# Power_SCH.net
KiCad netlist of a schematic drawn in Altium Designer
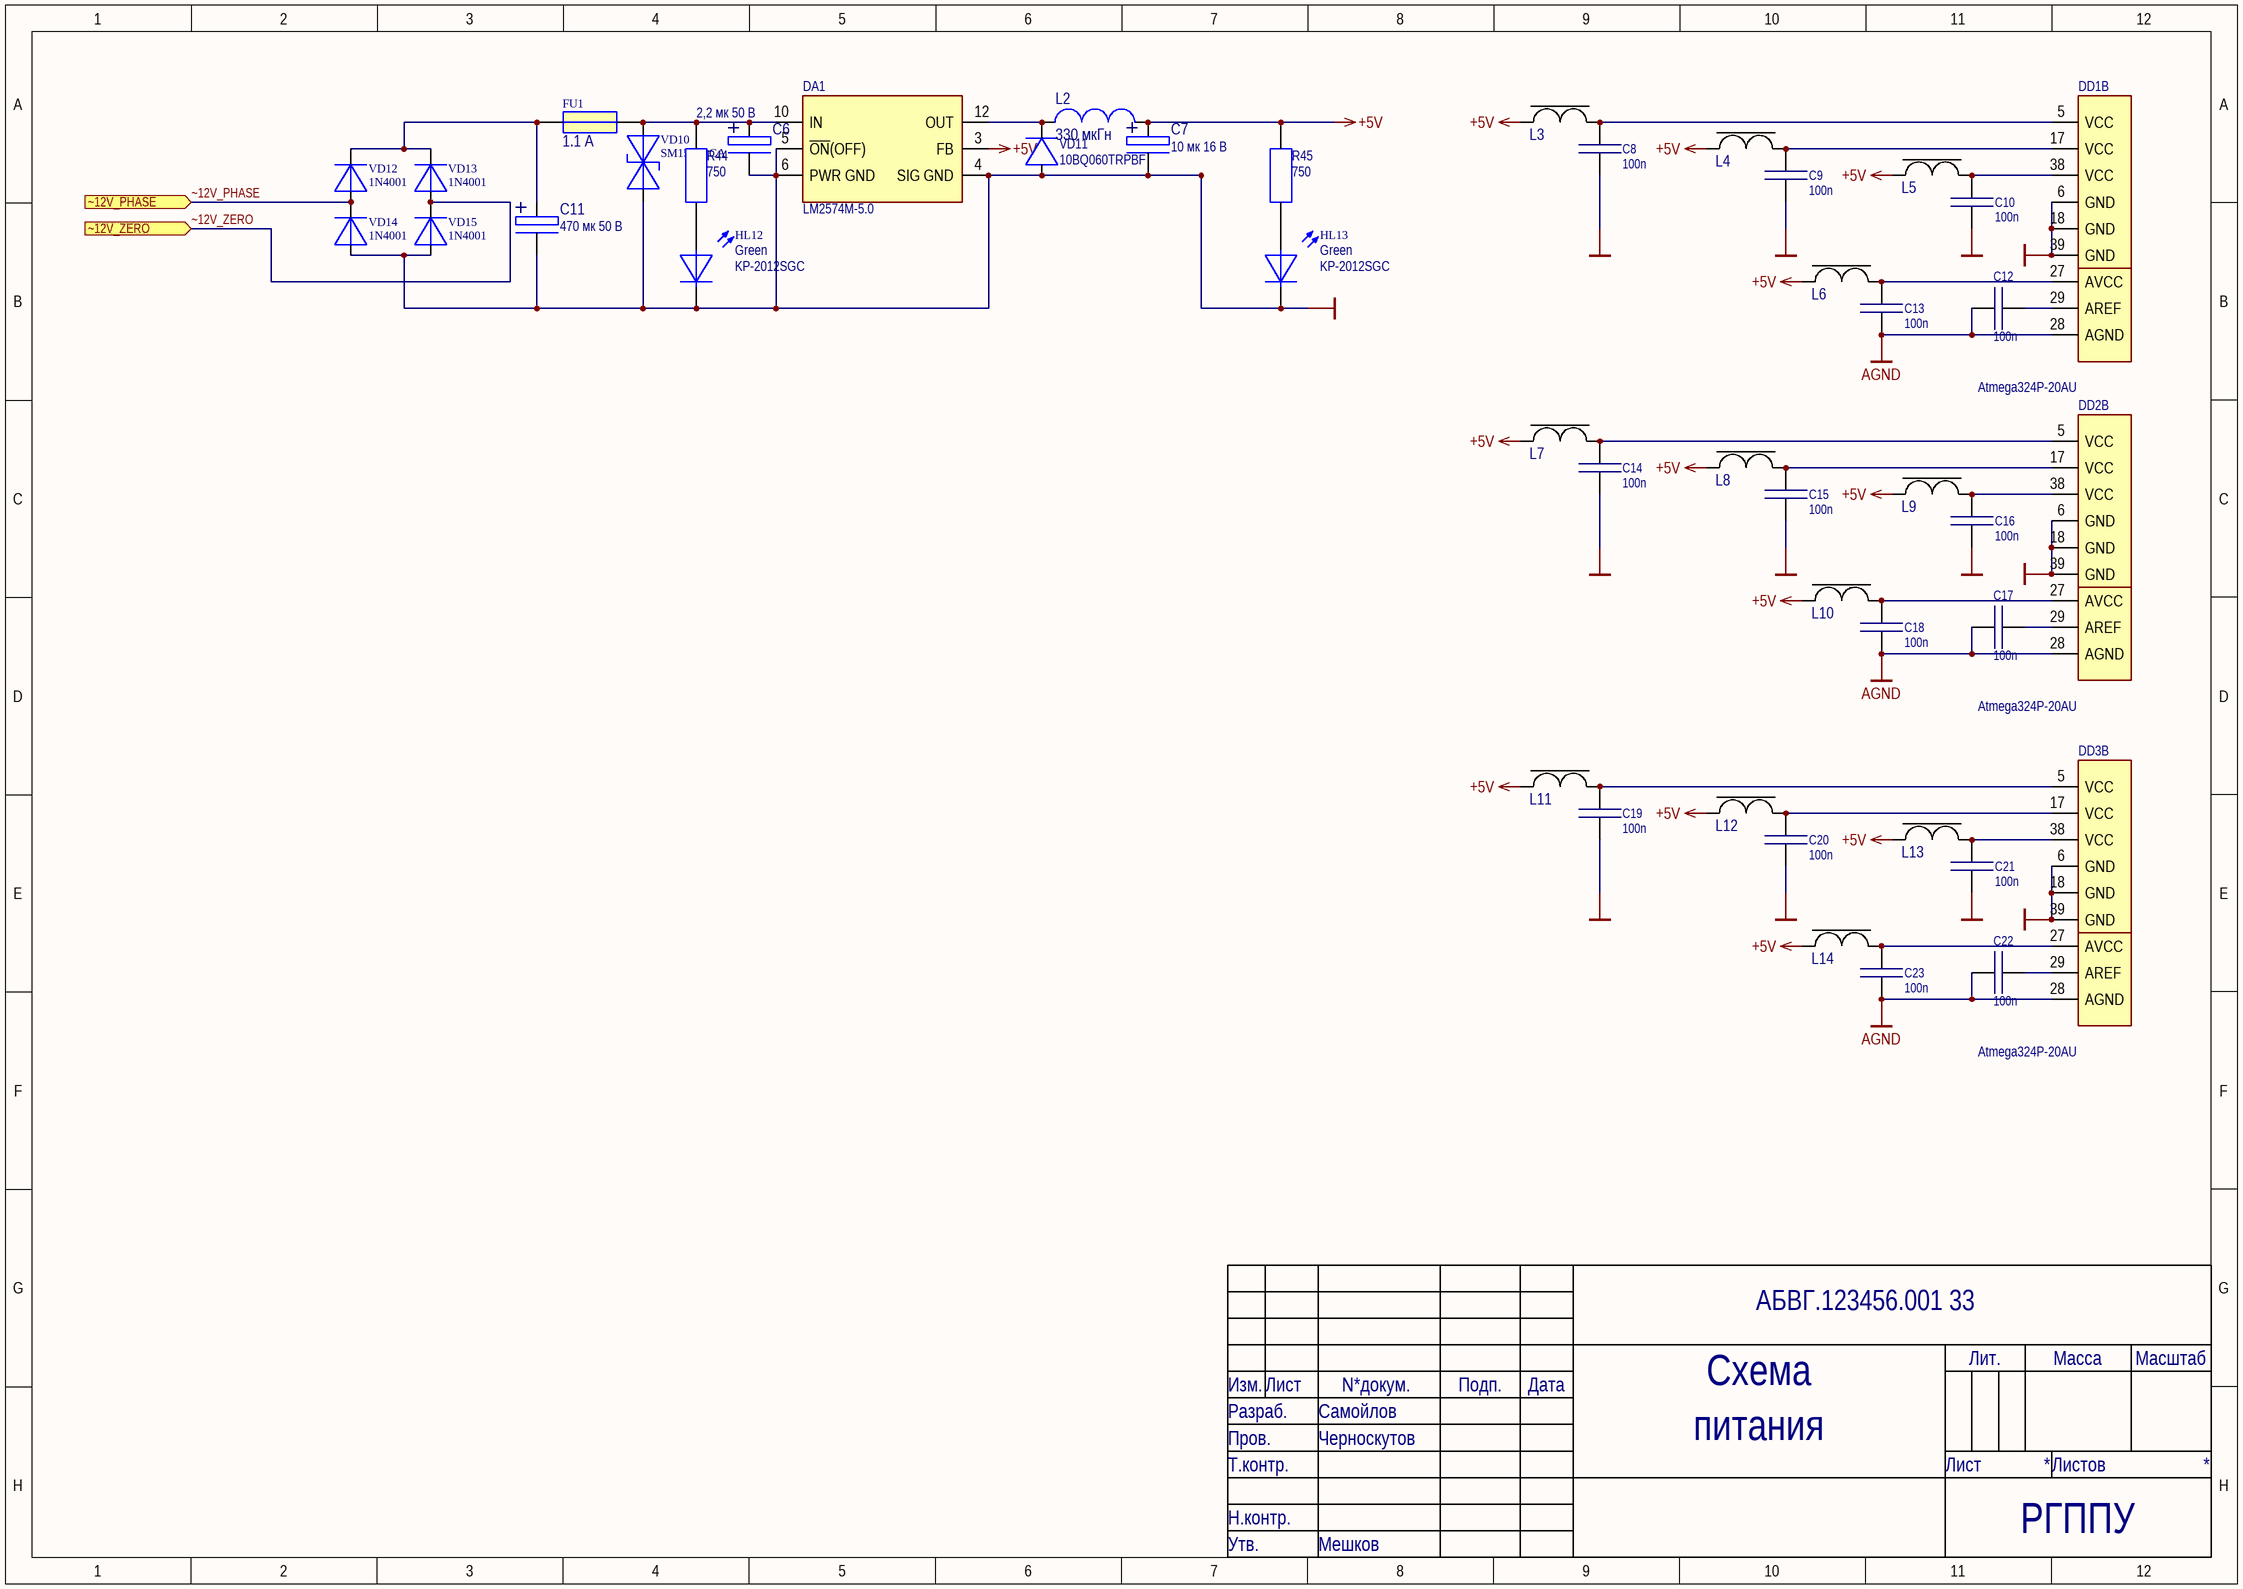
[diagram p0: Power_SCH.SchDoc]

(export (version "E")
  (design (tool "Eeschema 10.0.6"))
  (components
    (comp (ref "C6")
      (value "2,2 мк 50 В")
      (footprint "Cap:CAP_POLAR_ELLYTE_B")
      (description "2,2uF 50V Polar capacitor")
      (fields
        (field (name "MANUFACTURERPARTNUMBER") "CA050M2R20REB-0405")
        (field (name "MANUFACTURER") "Yageo")
      )
      (libsource (lib "Cap") (part "02200_050"))
    )
    (comp (ref "C7")
      (value "10 мк 16 В")
      (footprint "Cap:CAP_POLAR_ELLYTE_B")
      (description "10uF 16V Polar SMD cap")
      (fields
        (field (name "MANUFACTURERPARTNUMBER") "CA016M0010REB-0405")
        (field (name "MANUFACTURER") "YAGEO")
      )
      (libsource (lib "Cap") (part "10000_016"))
    )
    (comp (ref "C8")
      (value "100n")
      (footprint "SMDRC0805")
      (description "Generic capasitor non-polar")
      (fields (field (name "PARTNUMBER") "Capacitor 0805 100n"))
      (libsource (lib "library") (part "Capacitor"))
    )
    (comp (ref "C9")
      (value "100n")
      (footprint "SMDRC0805")
      (description "Generic capasitor non-polar")
      (fields (field (name "PARTNUMBER") "Capacitor 0805 100n"))
      (libsource (lib "library") (part "Capacitor"))
    )
    (comp (ref "C10")
      (value "100n")
      (footprint "SMDRC0805")
      (description "Generic capasitor non-polar")
      (fields (field (name "PARTNUMBER") "Capacitor 0805 100n"))
      (libsource (lib "library") (part "Capacitor"))
    )
    (comp (ref "C11")
      (value "470 мк 50 В")
      (footprint "Cap:CAP_POLAR_10mm")
      (description "470uF 50V Polar capacitor")
      (fields (field (name "MANUFACTURERPARTNUMBER") "CA035M0220REG") (field (name "MANUFACTURER") "Yageo"))
      (libsource (lib "Cap") (part "470000_050"))
    )
    (comp (ref "C12")
      (value "100n")
      (footprint "SMDRC0805")
      (description "Generic capasitor non-polar")
      (fields (field (name "PARTNUMBER") "Capacitor 0805 100n"))
      (libsource (lib "library") (part "Capacitor"))
    )
    (comp (ref "C13")
      (value "100n")
      (footprint "SMDRC0805")
      (description "Generic capasitor non-polar")
      (fields (field (name "PARTNUMBER") "Capacitor 0805 100n"))
      (libsource (lib "library") (part "Capacitor"))
    )
    (comp (ref "C14")
      (value "100n")
      (footprint "SMDRC0805")
      (description "Generic capasitor non-polar")
      (fields (field (name "PARTNUMBER") "Capacitor 0805 100n"))
      (libsource (lib "library") (part "Capacitor"))
    )
    (comp (ref "C15")
      (value "100n")
      (footprint "SMDRC0805")
      (description "Generic capasitor non-polar")
      (fields (field (name "PARTNUMBER") "Capacitor 0805 100n"))
      (libsource (lib "library") (part "Capacitor"))
    )
    (comp (ref "C16")
      (value "100n")
      (footprint "SMDRC0805")
      (description "Generic capasitor non-polar")
      (fields (field (name "PARTNUMBER") "Capacitor 0805 100n"))
      (libsource (lib "library") (part "Capacitor"))
    )
    (comp (ref "C17")
      (value "100n")
      (footprint "SMDRC0805")
      (description "Generic capasitor non-polar")
      (fields (field (name "PARTNUMBER") "Capacitor 0805 100n"))
      (libsource (lib "library") (part "Capacitor"))
    )
    (comp (ref "C18")
      (value "100n")
      (footprint "SMDRC0805")
      (description "Generic capasitor non-polar")
      (fields (field (name "PARTNUMBER") "Capacitor 0805 100n"))
      (libsource (lib "library") (part "Capacitor"))
    )
    (comp (ref "C19")
      (value "100n")
      (footprint "SMDRC0805")
      (description "Generic capasitor non-polar")
      (fields (field (name "PARTNUMBER") "Capacitor 0805 100n"))
      (libsource (lib "library") (part "Capacitor"))
    )
    (comp (ref "C20")
      (value "100n")
      (footprint "SMDRC0805")
      (description "Generic capasitor non-polar")
      (fields (field (name "PARTNUMBER") "Capacitor 0805 100n"))
      (libsource (lib "library") (part "Capacitor"))
    )
    (comp (ref "C21")
      (value "100n")
      (footprint "SMDRC0805")
      (description "Generic capasitor non-polar")
      (fields (field (name "PARTNUMBER") "Capacitor 0805 100n"))
      (libsource (lib "library") (part "Capacitor"))
    )
    (comp (ref "C22")
      (value "100n")
      (footprint "SMDRC0805")
      (description "Generic capasitor non-polar")
      (fields (field (name "PARTNUMBER") "Capacitor 0805 100n"))
      (libsource (lib "library") (part "Capacitor"))
    )
    (comp (ref "C23")
      (value "100n")
      (footprint "SMDRC0805")
      (description "Generic capasitor non-polar")
      (fields (field (name "PARTNUMBER") "Capacitor 0805 100n"))
      (libsource (lib "library") (part "Capacitor"))
    )
    (comp (ref "DA1")
      (value "LM2574M-5.0")
      (footprint "Power:SOIC127P1030X264-14M")
      (fields (field (name "MANUFACTURERPARTNUMBER") "LM2574M-5.0"))
      (libsource (lib "Power") (part "LM2574M-5.0"))
    )
    (comp (ref "DD1")
      (value "Atmega324P-20AU")
      (footprint "Atmel Microcontroller 8-Bit Automotive AVR:44ML_M")
      (description "Microcontroller 8-bit")
      (fields (field (name "MANUFACTURER") "Atmel") (field (name "MANUFACTURERPARTNUMBER") "Atmega324P-20AU"))
      (libsource (lib "Microcontrollers") (part "Atmega324P-20AU"))
    )
    (comp (ref "DD2")
      (value "Atmega324P-20AU")
      (footprint "Atmel Microcontroller 8-Bit Automotive AVR:44ML_M")
      (description "Microcontroller 8-bit")
      (fields (field (name "MANUFACTURER") "Atmel") (field (name "MANUFACTURERPARTNUMBER") "Atmega324P-20AU"))
      (libsource (lib "Microcontrollers") (part "Atmega324P-20AU"))
    )
    (comp (ref "DD3")
      (value "Atmega324P-20AU")
      (footprint "Atmel Microcontroller 8-Bit Automotive AVR:44ML_M")
      (description "Microcontroller 8-bit")
      (fields (field (name "MANUFACTURER") "Atmel") (field (name "MANUFACTURERPARTNUMBER") "Atmega324P-20AU"))
      (libsource (lib "Microcontrollers") (part "Atmega324P-20AU"))
    )
    (comp (ref "FU1")
      (value "1.1 А")
      (footprint "Power:EFuse 1.1A")
      (description "Fuse")
      (fields (field (name "MANUFACTURERPARTNUMBER") "EFuse LP60-110F"))
      (libsource (lib "Power") (part "EFuse LP60-110F"))
    )
    (comp (ref "HL12")
      (value "Green")
      (footprint "Indicator:DIOMELF2012M")
      (description "Diod LED SMD Green")
      (fields (field (name "MANUFACTURERPARTNUMBER") "KP-2012SGC"))
      (libsource (lib "Indicator") (part "LED1_G"))
    )
    (comp (ref "HL13")
      (value "Green")
      (footprint "Indicator:DIOMELF2012M")
      (description "Diod LED SMD Green")
      (fields (field (name "MANUFACTURERPARTNUMBER") "KP-2012SGC"))
      (libsource (lib "Indicator") (part "LED1_G"))
    )
    (comp (ref "L2")
      (value "330 мкГн")
      (footprint "Inductor:INDP7972X50M")
      (description "Inductor")
      (fields (field (name "MANUFACTURERPARTNUMBER") "SCD0705T-331K-N"))
      (libsource (lib "Inductor") (part "SCD0705T-331K-N"))
    )
    (comp (ref "L3")
      (value "MPZ1608S181A")
      (footprint "Inductor:INDC0603X03M")
      (description "Ferrite Bead")
      (libsource (lib "Inductor") (part "Ferrite Bead"))
    )
    (comp (ref "L4")
      (value "MPZ1608S181A")
      (footprint "Inductor:INDC0603X03M")
      (description "Ferrite Bead")
      (libsource (lib "Inductor") (part "Ferrite Bead"))
    )
    (comp (ref "L5")
      (value "MPZ1608S181A")
      (footprint "Inductor:INDC0603X03M")
      (description "Ferrite Bead")
      (libsource (lib "Inductor") (part "Ferrite Bead"))
    )
    (comp (ref "L6")
      (value "MPZ1608S181A")
      (footprint "Inductor:INDC0603X03M")
      (description "Ferrite Bead")
      (libsource (lib "Inductor") (part "Ferrite Bead"))
    )
    (comp (ref "L7")
      (value "MPZ1608S181A")
      (footprint "Inductor:INDC0603X03M")
      (description "Ferrite Bead")
      (libsource (lib "Inductor") (part "Ferrite Bead"))
    )
    (comp (ref "L8")
      (value "MPZ1608S181A")
      (footprint "Inductor:INDC0603X03M")
      (description "Ferrite Bead")
      (libsource (lib "Inductor") (part "Ferrite Bead"))
    )
    (comp (ref "L9")
      (value "MPZ1608S181A")
      (footprint "Inductor:INDC0603X03M")
      (description "Ferrite Bead")
      (libsource (lib "Inductor") (part "Ferrite Bead"))
    )
    (comp (ref "L10")
      (value "MPZ1608S181A")
      (footprint "Inductor:INDC0603X03M")
      (description "Ferrite Bead")
      (libsource (lib "Inductor") (part "Ferrite Bead"))
    )
    (comp (ref "L11")
      (value "MPZ1608S181A")
      (footprint "Inductor:INDC0603X03M")
      (description "Ferrite Bead")
      (libsource (lib "Inductor") (part "Ferrite Bead"))
    )
    (comp (ref "L12")
      (value "MPZ1608S181A")
      (footprint "Inductor:INDC0603X03M")
      (description "Ferrite Bead")
      (libsource (lib "Inductor") (part "Ferrite Bead"))
    )
    (comp (ref "L13")
      (value "MPZ1608S181A")
      (footprint "Inductor:INDC0603X03M")
      (description "Ferrite Bead")
      (libsource (lib "Inductor") (part "Ferrite Bead"))
    )
    (comp (ref "L14")
      (value "MPZ1608S181A")
      (footprint "Inductor:INDC0603X03M")
      (description "Ferrite Bead")
      (libsource (lib "Inductor") (part "Ferrite Bead"))
    )
    (comp (ref "R44")
      (value "750")
      (footprint "SMDRC0805")
      (description "Generic resistor")
      (fields (field (name "PARTNUMBER") "Resistor 0805 750"))
      (libsource (lib "library") (part "Resistor"))
    )
    (comp (ref "R45")
      (value "750")
      (footprint "SMDRC0805")
      (description "Generic resistor")
      (fields (field (name "PARTNUMBER") "Resistor 0805 750"))
      (libsource (lib "library") (part "Resistor"))
    )
    (comp (ref "VD10")
      (value "SM15T12CA")
      (footprint "DIod:SUPRES3216X18N")
      (description "Diod suppressor")
      (fields
        (field (name "MANUFACTURER") "ST Microelectronics")
        (field (name "MANUFACTURERPARTNUMBER") "SM15T12CA")
      )
      (libsource (lib "Diod") (part "SM15T12CA"))
    )
    (comp (ref "VD11")
      (value "10BQ060TRPBF")
      (footprint "DIod:SHOTKY 4.1x3.3")
      (description "DIODE SCHOTTKY 60V 1A DO214AA")
      (fields
        (field (name "MANUFACTURER") "Vishay Semiconductor Diodes Division")
        (field (name "MANUFACTURERPARTNUMBER") "10BQ060TRPBF")
      )
      (libsource (lib "Diod") (part "10BQ060TRPBF"))
    )
    (comp (ref "VD12")
      (value "1N4001")
      (footprint "DIod:PinDiode")
      (description "Rectifying diode")
      (fields (field (name "MANUFACTURERPARTNUMBER") "1N4001"))
      (libsource (lib "Diod") (part "1N4001"))
    )
    (comp (ref "VD13")
      (value "1N4001")
      (footprint "DIod:PinDiode")
      (description "Rectifying diode")
      (fields (field (name "MANUFACTURERPARTNUMBER") "1N4001"))
      (libsource (lib "Diod") (part "1N4001"))
    )
    (comp (ref "VD14")
      (value "1N4001")
      (footprint "DIod:PinDiode")
      (description "Rectifying diode")
      (fields (field (name "MANUFACTURERPARTNUMBER") "1N4001"))
      (libsource (lib "Diod") (part "1N4001"))
    )
    (comp (ref "VD15")
      (value "1N4001")
      (footprint "DIod:PinDiode")
      (description "Rectifying diode")
      (fields (field (name "MANUFACTURERPARTNUMBER") "1N4001"))
      (libsource (lib "Diod") (part "1N4001"))
    )
  )
  (nets
    (net (code "1") (name "+5V") (class "Default")
      (node (ref "C7") (pin "2") (pinfunction "+_2") (pintype "passive"))
      (node (ref "DA1") (pin "3") (pinfunction "FB_3") (pintype "passive"))
      (node (ref "L10") (pin "1") (pinfunction "1_1") (pintype "passive"))
      (node (ref "L11") (pin "1") (pinfunction "1_1") (pintype "passive"))
      (node (ref "L12") (pin "1") (pinfunction "1_1") (pintype "passive"))
      (node (ref "L13") (pin "1") (pinfunction "1_1") (pintype "passive"))
      (node (ref "L14") (pin "1") (pinfunction "1_1") (pintype "passive"))
      (node (ref "L2") (pin "1") (pinfunction "1_1") (pintype "passive"))
      (node (ref "L3") (pin "1") (pinfunction "1_1") (pintype "passive"))
      (node (ref "L4") (pin "1") (pinfunction "1_1") (pintype "passive"))
      (node (ref "L5") (pin "1") (pinfunction "1_1") (pintype "passive"))
      (node (ref "L6") (pin "1") (pinfunction "1_1") (pintype "passive"))
      (node (ref "L7") (pin "1") (pinfunction "1_1") (pintype "passive"))
      (node (ref "L8") (pin "1") (pinfunction "1_1") (pintype "passive"))
      (node (ref "L9") (pin "1") (pinfunction "1_1") (pintype "passive"))
      (node (ref "R45") (pin "2") (pinfunction "2_2") (pintype "passive"))
    )
    (net (code "2") (name "/~12V_PHASE") (class "Default")
      (node (ref "VD12") (pin "A") (pinfunction "A_A") (pintype "passive"))
      (node (ref "VD14") (pin "K") (pinfunction "K_K") (pintype "passive"))
    )
    (net (code "3") (name "/~12V_ZERO") (class "Default")
      (node (ref "VD13") (pin "A") (pinfunction "A_A") (pintype "passive"))
      (node (ref "VD15") (pin "K") (pinfunction "K_K") (pintype "passive"))
    )
    (net (code "4") (name "AGND") (class "Default")
      (node (ref "C12") (pin "1") (pintype "passive"))
      (node (ref "C13") (pin "1") (pintype "passive"))
      (node (ref "C17") (pin "1") (pintype "passive"))
      (node (ref "C18") (pin "1") (pintype "passive"))
      (node (ref "C22") (pin "1") (pintype "passive"))
      (node (ref "C23") (pin "1") (pintype "passive"))
      (node (ref "DD1") (pin "28") (pinfunction "AGND_28") (pintype "power_in"))
      (node (ref "DD2") (pin "28") (pinfunction "AGND_28") (pintype "power_in"))
      (node (ref "DD3") (pin "28") (pinfunction "AGND_28") (pintype "power_in"))
    )
    (net (code "5") (name "GND") (class "Default")
      (node (ref "C10") (pin "1") (pintype "passive"))
      (node (ref "C11") (pin "1") (pinfunction "-_1") (pintype "passive"))
      (node (ref "C14") (pin "1") (pintype "passive"))
      (node (ref "C15") (pin "1") (pintype "passive"))
      (node (ref "C16") (pin "1") (pintype "passive"))
      (node (ref "C19") (pin "1") (pintype "passive"))
      (node (ref "C20") (pin "1") (pintype "passive"))
      (node (ref "C21") (pin "1") (pintype "passive"))
      (node (ref "C6") (pin "1") (pinfunction "-_1") (pintype "passive"))
      (node (ref "C7") (pin "1") (pinfunction "-_1") (pintype "passive"))
      (node (ref "C8") (pin "1") (pintype "passive"))
      (node (ref "C9") (pin "1") (pintype "passive"))
      (node (ref "DA1") (pin "4") (pinfunction "SIG_GND_4") (pintype "passive"))
      (node (ref "DA1") (pin "5") (pinfunction "~{ON}(OFF)_5") (pintype "passive"))
      (node (ref "DA1") (pin "6") (pinfunction "PWR_GND_6") (pintype "passive"))
      (node (ref "DD1") (pin "18") (pinfunction "GND_18") (pintype "power_in"))
      (node (ref "DD1") (pin "39") (pinfunction "GND_39") (pintype "power_in"))
      (node (ref "DD1") (pin "6") (pinfunction "GND_6") (pintype "power_in"))
      (node (ref "DD2") (pin "18") (pinfunction "GND_18") (pintype "power_in"))
      (node (ref "DD2") (pin "39") (pinfunction "GND_39") (pintype "power_in"))
      (node (ref "DD2") (pin "6") (pinfunction "GND_6") (pintype "power_in"))
      (node (ref "DD3") (pin "18") (pinfunction "GND_18") (pintype "power_in"))
      (node (ref "DD3") (pin "39") (pinfunction "GND_39") (pintype "power_in"))
      (node (ref "DD3") (pin "6") (pinfunction "GND_6") (pintype "power_in"))
      (node (ref "HL12") (pin "2") (pinfunction "2_2") (pintype "passive"))
      (node (ref "HL13") (pin "2") (pinfunction "2_2") (pintype "passive"))
      (node (ref "VD10") (pin "1") (pinfunction "1_1") (pintype "passive"))
      (node (ref "VD11") (pin "A") (pinfunction "A_A") (pintype "passive"))
      (node (ref "VD14") (pin "A") (pinfunction "A_A") (pintype "passive"))
      (node (ref "VD15") (pin "A") (pinfunction "A_A") (pintype "passive"))
    )
    (net (code "6") (name "Net-(C6-+)") (class "Default")
      (node (ref "C6") (pin "2") (pinfunction "+_2") (pintype "passive"))
      (node (ref "DA1") (pin "10") (pinfunction "IN_10") (pintype "passive"))
      (node (ref "FU1") (pin "2") (pinfunction "2_2") (pintype "passive"))
      (node (ref "R44") (pin "2") (pinfunction "2_2") (pintype "passive"))
      (node (ref "VD10") (pin "2") (pinfunction "2_2") (pintype "passive"))
    )
    (net (code "7") (name "Net-(C8-Pad2)") (class "Default")
      (node (ref "C8") (pin "2") (pintype "passive"))
      (node (ref "DD1") (pin "5") (pinfunction "VCC_5") (pintype "power_in"))
      (node (ref "L3") (pin "2") (pinfunction "2_2") (pintype "passive"))
    )
    (net (code "8") (name "Net-(C9-Pad2)") (class "Default")
      (node (ref "C9") (pin "2") (pintype "passive"))
      (node (ref "DD1") (pin "17") (pinfunction "VCC_17") (pintype "power_in"))
      (node (ref "L4") (pin "2") (pinfunction "2_2") (pintype "passive"))
    )
    (net (code "9") (name "Net-(C10-Pad2)") (class "Default")
      (node (ref "C10") (pin "2") (pintype "passive"))
      (node (ref "DD1") (pin "38") (pinfunction "VCC_38") (pintype "power_in"))
      (node (ref "L5") (pin "2") (pinfunction "2_2") (pintype "passive"))
    )
    (net (code "10") (name "Net-(C11-+)") (class "Default")
      (node (ref "C11") (pin "2") (pinfunction "+_2") (pintype "passive"))
      (node (ref "FU1") (pin "1") (pinfunction "1_1") (pintype "passive"))
      (node (ref "VD12") (pin "K") (pinfunction "K_K") (pintype "passive"))
      (node (ref "VD13") (pin "K") (pinfunction "K_K") (pintype "passive"))
    )
    (net (code "11") (name "Net-(C14-Pad2)") (class "Default")
      (node (ref "C14") (pin "2") (pintype "passive"))
      (node (ref "DD2") (pin "5") (pinfunction "VCC_5") (pintype "power_in"))
      (node (ref "L7") (pin "2") (pinfunction "2_2") (pintype "passive"))
    )
    (net (code "12") (name "Net-(C15-Pad2)") (class "Default")
      (node (ref "C15") (pin "2") (pintype "passive"))
      (node (ref "DD2") (pin "17") (pinfunction "VCC_17") (pintype "power_in"))
      (node (ref "L8") (pin "2") (pinfunction "2_2") (pintype "passive"))
    )
    (net (code "13") (name "Net-(C16-Pad2)") (class "Default")
      (node (ref "C16") (pin "2") (pintype "passive"))
      (node (ref "DD2") (pin "38") (pinfunction "VCC_38") (pintype "power_in"))
      (node (ref "L9") (pin "2") (pinfunction "2_2") (pintype "passive"))
    )
    (net (code "14") (name "Net-(C19-Pad2)") (class "Default")
      (node (ref "C19") (pin "2") (pintype "passive"))
      (node (ref "DD3") (pin "5") (pinfunction "VCC_5") (pintype "power_in"))
      (node (ref "L11") (pin "2") (pinfunction "2_2") (pintype "passive"))
    )
    (net (code "15") (name "Net-(C20-Pad2)") (class "Default")
      (node (ref "C20") (pin "2") (pintype "passive"))
      (node (ref "DD3") (pin "17") (pinfunction "VCC_17") (pintype "power_in"))
      (node (ref "L12") (pin "2") (pinfunction "2_2") (pintype "passive"))
    )
    (net (code "16") (name "Net-(C21-Pad2)") (class "Default")
      (node (ref "C21") (pin "2") (pintype "passive"))
      (node (ref "DD3") (pin "38") (pinfunction "VCC_38") (pintype "power_in"))
      (node (ref "L13") (pin "2") (pinfunction "2_2") (pintype "passive"))
    )
    (net (code "17") (name "Net-(DA1-OUT)") (class "Default")
      (node (ref "DA1") (pin "12") (pinfunction "OUT_12") (pintype "passive"))
      (node (ref "L2") (pin "2") (pinfunction "2_2") (pintype "passive"))
      (node (ref "VD11") (pin "K") (pinfunction "K_K") (pintype "passive"))
    )
    (net (code "18") (name "Net-(DD1B-AREF)") (class "Default")
      (node (ref "C12") (pin "2") (pintype "passive"))
      (node (ref "DD1") (pin "29") (pinfunction "AREF_29") (pintype "power_in"))
    )
    (net (code "19") (name "Net-(DD1B-AVCC)") (class "Default")
      (node (ref "C13") (pin "2") (pintype "passive"))
      (node (ref "DD1") (pin "27") (pinfunction "AVCC_27") (pintype "power_in"))
      (node (ref "L6") (pin "2") (pinfunction "2_2") (pintype "passive"))
    )
    (net (code "20") (name "Net-(DD2B-AREF)") (class "Default")
      (node (ref "C17") (pin "2") (pintype "passive"))
      (node (ref "DD2") (pin "29") (pinfunction "AREF_29") (pintype "power_in"))
    )
    (net (code "21") (name "Net-(DD2B-AVCC)") (class "Default")
      (node (ref "C18") (pin "2") (pintype "passive"))
      (node (ref "DD2") (pin "27") (pinfunction "AVCC_27") (pintype "power_in"))
      (node (ref "L10") (pin "2") (pinfunction "2_2") (pintype "passive"))
    )
    (net (code "22") (name "Net-(DD3B-AREF)") (class "Default")
      (node (ref "C22") (pin "2") (pintype "passive"))
      (node (ref "DD3") (pin "29") (pinfunction "AREF_29") (pintype "power_in"))
    )
    (net (code "23") (name "Net-(DD3B-AVCC)") (class "Default")
      (node (ref "C23") (pin "2") (pintype "passive"))
      (node (ref "DD3") (pin "27") (pinfunction "AVCC_27") (pintype "power_in"))
      (node (ref "L14") (pin "2") (pinfunction "2_2") (pintype "passive"))
    )
    (net (code "24") (name "Net-(HL12-Pad1)") (class "Default")
      (node (ref "HL12") (pin "1") (pinfunction "1_1") (pintype "passive"))
      (node (ref "R44") (pin "1") (pinfunction "1_1") (pintype "passive"))
    )
    (net (code "25") (name "Net-(HL13-Pad1)") (class "Default")
      (node (ref "HL13") (pin "1") (pinfunction "1_1") (pintype "passive"))
      (node (ref "R45") (pin "1") (pinfunction "1_1") (pintype "passive"))
    )
  )
)
